# CAN_IFC.net
KiCad netlist of a schematic drawn in Altium Designer
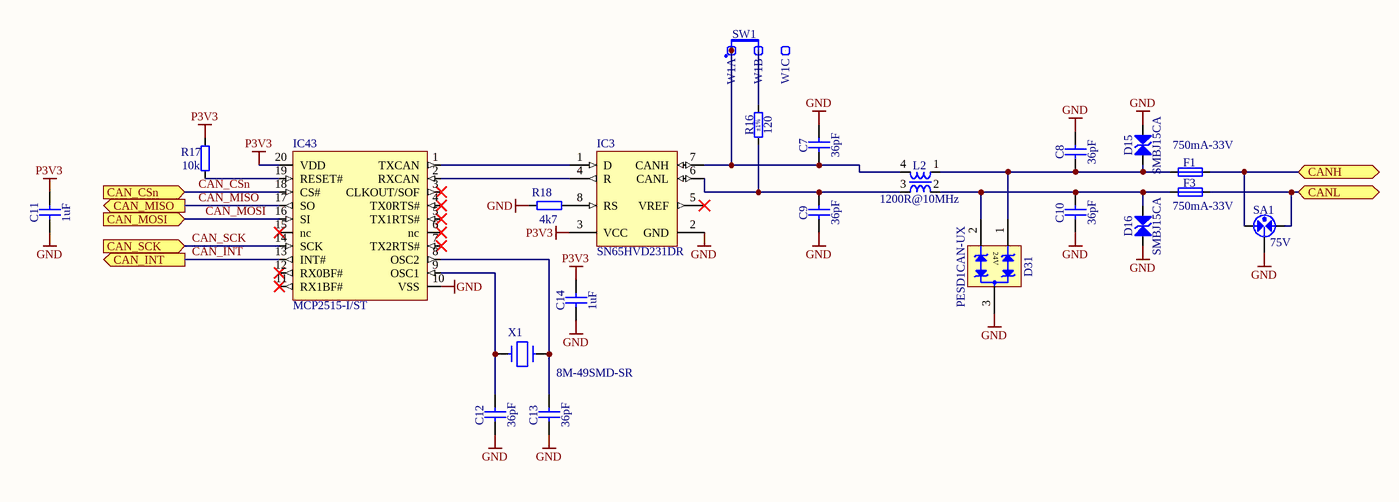
[diagram p0: CAN_IFC.SchDoc]

(export (version "E")
  (design (tool "Eeschema 10.0.6"))
  (components
    (comp (ref "C7")
      (value "36pF")
      (footprint "CAPC1608X87N")
      (description "Non-polarised capacitor")
      (fields
        (field (name "PART NUMBER") "CC0603_36PF_50V_5%_C0G")
        (field (name "VOLTAGE") "50V")
        (field (name "AUTHOR") "CERN DEM HF")
      )
      (libsource (lib "Capacitors") (part "Capacitor - non polarized"))
    )
    (comp (ref "C8")
      (value "36pF")
      (footprint "CAPC1608X87N")
      (description "Non-polarised capacitor")
      (fields
        (field (name "PART NUMBER") "CC0603_36PF_50V_5%_C0G")
        (field (name "VOLTAGE") "50V")
        (field (name "AUTHOR") "CERN DEM HF")
      )
      (libsource (lib "Capacitors") (part "Capacitor - non polarized"))
    )
    (comp (ref "C9")
      (value "36pF")
      (footprint "CAPC1608X87N")
      (description "Non-polarised capacitor")
      (fields
        (field (name "PART NUMBER") "CC0603_36PF_50V_5%_C0G")
        (field (name "VOLTAGE") "50V")
        (field (name "AUTHOR") "CERN DEM HF")
      )
      (libsource (lib "Capacitors") (part "Capacitor - non polarized"))
    )
    (comp (ref "C10")
      (value "36pF")
      (footprint "CAPC1608X87N")
      (description "Non-polarised capacitor")
      (fields
        (field (name "PART NUMBER") "CC0603_36PF_50V_5%_C0G")
        (field (name "VOLTAGE") "50V")
        (field (name "AUTHOR") "CERN DEM HF")
      )
      (libsource (lib "Capacitors") (part "Capacitor - non polarized"))
    )
    (comp (ref "C11")
      (value "1uF")
      (footprint "CAPC1608X87N")
      (description "Non-polarised capacitor")
      (fields
        (field (name "PART NUMBER") "CC0603_1UF_25V_10%_X7R")
        (field (name "VOLTAGE") "25V")
        (field (name "AUTHOR") "CERN DEM JLC")
      )
      (libsource (lib "Capacitors") (part "Capacitor - non polarized"))
    )
    (comp (ref "C12")
      (value "36pF")
      (footprint "CAPC1608X87N")
      (description "Non-polarised capacitor")
      (fields
        (field (name "PART NUMBER") "CC0603_36PF_50V_5%_C0G")
        (field (name "VOLTAGE") "50V")
        (field (name "AUTHOR") "CERN DEM HF")
      )
      (libsource (lib "Capacitors") (part "Capacitor - non polarized"))
    )
    (comp (ref "C13")
      (value "36pF")
      (footprint "CAPC1608X87N")
      (description "Non-polarised capacitor")
      (fields
        (field (name "PART NUMBER") "CC0603_36PF_50V_5%_C0G")
        (field (name "VOLTAGE") "50V")
        (field (name "AUTHOR") "CERN DEM HF")
      )
      (libsource (lib "Capacitors") (part "Capacitor - non polarized"))
    )
    (comp (ref "C14")
      (value "1uF")
      (footprint "CAPC1608X87N")
      (description "Non-polarised capacitor")
      (fields
        (field (name "PART NUMBER") "CC0603_1UF_25V_10%_X7R")
        (field (name "VOLTAGE") "25V")
        (field (name "AUTHOR") "CERN DEM JLC")
      )
      (libsource (lib "Capacitors") (part "Capacitor - non polarized"))
    )
    (comp (ref "D15")
      (value "SMBJ15CA")
      (footprint "DIOM5336X265N")
      (description "Transient Voltage Suppressor Diode (Bi-Directional)")
      (fields
        (field (name "VOLTAGE") "15V")
        (field (name "POWER") "600W")
        (field (name "AUTHOR") "CERN DEM JLC")
      )
      (libsource (lib "ICs And Semiconductors") (part "Diode TVS Bi-Directional"))
    )
    (comp (ref "D16")
      (value "SMBJ15CA")
      (footprint "DIOM5336X265N")
      (description "Transient Voltage Suppressor Diode (Bi-Directional)")
      (fields
        (field (name "VOLTAGE") "15V")
        (field (name "POWER") "600W")
        (field (name "AUTHOR") "CERN DEM JLC")
      )
      (libsource (lib "ICs And Semiconductors") (part "Diode TVS Bi-Directional"))
    )
    (comp (ref "D31")
      (value "PESD1CAN-UX")
      (footprint "SOT95P237X112-3N")
      (description "TVS Diode for CAN")
      (fields
        (field (name "VOLTAGE") "24V")
        (field (name "POWER") "400W")
        (field (name "AUTHOR") "CERN DEM JLC")
      )
      (libsource (lib "LIBRARY_SCH") (part "D_TVS_PESD1CAN"))
    )
    (comp (ref "F1")
      (value "750mA-33V")
      (footprint "FUSRC4632X150N")
      (description "Fuse")
      (fields
        (field (name "PART NUMBER") "FUSR1812_LITTELFUSE_miniSMDC075F/33")
        (field (name "MANUFACTURER") "LITTELFUSE")
        (field (name "AUTHOR") "CERN DEM HF")
      )
      (libsource (lib "Eletro-mechanical") (part "Fuse"))
    )
    (comp (ref "F3")
      (value "750mA-33V")
      (footprint "FUSRC4632X150N")
      (description "Fuse")
      (fields
        (field (name "PART NUMBER") "FUSR1812_LITTELFUSE_miniSMDC075F/33")
        (field (name "MANUFACTURER") "LITTELFUSE")
        (field (name "AUTHOR") "CERN DEM HF")
      )
      (libsource (lib "Eletro-mechanical") (part "Fuse"))
    )
    (comp (ref "IC3")
      (value "SN65HVD231DR")
      (footprint "D0008A_L")
      (fields (field (name "MANUFACTURER") "Texas Instruments"))
      (libsource (lib "Altium Content Vault") (part "TI-SN65HVD231-SOIC_D-8"))
    )
    (comp (ref "IC43")
      (value "MCP2515-I/ST")
      (footprint "SOP65P640X110-20N")
      (description "CAN Controller With SPI nterface")
      (fields
        (field (name "MANUFACTURER") "Microchip")
        (field (name "MANUFACTURER PART NUMBER") "MCP2515T-I/ST")
      )
      (libsource (lib "LIBRARY_SCH") (part "IFC_MCP2515_TSSOP"))
    )
    (comp (ref "L2")
      (value "1200R@10MHz")
      (footprint "IND_TDK_ACT45B")
      (description "Inductor Common Mode")
      (fields
        (field (name "PART NUMBER") "IND_TDK_ACT45B-220-2P")
        (field (name "POWER") "200mA")
        (field (name "AUTHOR") "CERN DEM BC")
      )
      (libsource (lib "Inductors & Transformers") (part "Inductor Common Mode 1-4 2-3"))
    )
    (comp (ref "R16")
      (value "120")
      (footprint "RESC3216X65N")
      (description "Resistor - 1%")
      (fields
        (field (name "TOLERANCE") "±1%")
        (field (name "PART NUMBER") "R1206_120R_1%_0.25W_100PPM")
        (field (name "POWER") "0.25W")
        (field (name "AUTHOR") "CERN DEM JLC")
      )
      (libsource (lib "Resistors") (part "Resistor - 1%"))
    )
    (comp (ref "R17")
      (value "10k")
      (footprint "RESC1608X55N")
      (description "Resistor - 1%")
      (fields
        (field (name "PART NUMBER") "R0603_10K_1%_0.1W_100PPM")
        (field (name "POWER") "0.1W")
        (field (name "AUTHOR") "CERN DEM JLC")
      )
      (libsource (lib "Resistors") (part "Resistor - 1%"))
    )
    (comp (ref "R18")
      (value "4k7")
      (footprint "RESC1608X55N")
      (description "Resistor - 1%")
      (fields
        (field (name "PART NUMBER") "R0603_4K7_1%_0.1W_100PPM")
        (field (name "POWER") "0.1W")
        (field (name "AUTHOR") "CERN DEM JLC")
      )
      (libsource (lib "Resistors") (part "Resistor - 1%"))
    )
    (comp (ref "SA1")
      (value "75V")
      (footprint "SAR_BOURNS_2036-xx-SM")
      (description "Surge Arrester")
      (fields
        (field (name "PART NUMBER") "SAR_BOURNS_2036-07-SMLF")
        (field (name "MANUFACTURER") "BOURNS")
        (field (name "AUTHOR") "CERN DEM JLC")
      )
      (libsource (lib "Eletro-mechanical") (part "Surge Arrester Type2"))
    )
    (comp (ref "SW1")
      (value "Jumper Type1")
      (footprint "JUMPER_BLACK_INSULATED_2.54MM")
      (description "Jumper 1 Pin")
      (fields
        (field (name "PART NUMBER") "COMATEL_313.1730.0.00.40.0")
        (field (name "MANUFACTURER") "KONTEK COMATEL")
        (field (name "AUTHOR") "CERN DEM JLC")
      )
      (libsource (lib "Connectors") (part "Jumper Type1"))
    )
    (comp (ref "W1")
      (value "Test Point")
      (footprint "COMATEL_385.0358.1.03.400")
      (description "3 Mini Wire-Wrap Contact Strip Header")
      (fields
        (field (name "PART NUMBER") "COMATEL_385.0358.1.03.400")
        (field (name "MANUFACTURER") "KONTEK COMATEL")
        (field (name "AUTHOR") "CERN DEM JLC")
      )
      (libsource (lib "Connectors") (part "Wire-Wrap Contact x3"))
    )
    (comp (ref "X1")
      (value "8M-49SMD-SR")
      (footprint "HC-49SM")
      (description "8MHz; ±30ppm; 20pF; SMD; HC49SMD")
      (libsource (lib "Crystals_Oscillators") (part "X_CRYSTAL_HC49_SMT"))
    )
  )
  (nets
    (net (code "1") (name "/CANH") (class "Default")
      (node (ref "F1") (pin "2") (pinfunction "2_2") (pintype "passive"))
      (node (ref "SA1") (pin "1") (pinfunction "1_1") (pintype "passive"))
    )
    (net (code "2") (name "/CANL") (class "Default")
      (node (ref "F3") (pin "2") (pinfunction "2_2") (pintype "passive"))
      (node (ref "SA1") (pin "2") (pinfunction "2_2") (pintype "passive"))
    )
    (net (code "3") (name "/CAN_CSn") (class "Default")
      (node (ref "IC43") (pin "18") (pinfunction "CS#_18") (pintype "input"))
    )
    (net (code "4") (name "/CAN_INT") (class "Default")
      (node (ref "IC43") (pin "13") (pinfunction "INT#_13") (pintype "output"))
    )
    (net (code "5") (name "/CAN_MISO") (class "Default")
      (node (ref "IC43") (pin "17") (pinfunction "SO_17") (pintype "output"))
    )
    (net (code "6") (name "/CAN_MOSI") (class "Default")
      (node (ref "IC43") (pin "16") (pinfunction "SI_16") (pintype "input"))
    )
    (net (code "7") (name "/CAN_SCK") (class "Default")
      (node (ref "IC43") (pin "14") (pinfunction "SCK_14") (pintype "input"))
    )
    (net (code "8") (name "GND") (class "Default")
      (node (ref "C10") (pin "1") (pinfunction "1_1") (pintype "passive"))
      (node (ref "C11") (pin "1") (pinfunction "1_1") (pintype "passive"))
      (node (ref "C12") (pin "1") (pinfunction "1_1") (pintype "passive"))
      (node (ref "C13") (pin "1") (pinfunction "1_1") (pintype "passive"))
      (node (ref "C14") (pin "1") (pinfunction "1_1") (pintype "passive"))
      (node (ref "C7") (pin "2") (pinfunction "2_2") (pintype "passive"))
      (node (ref "C8") (pin "2") (pinfunction "2_2") (pintype "passive"))
      (node (ref "C9") (pin "1") (pinfunction "1_1") (pintype "passive"))
      (node (ref "D15") (pin "2") (pinfunction "2_2") (pintype "passive"))
      (node (ref "D16") (pin "1") (pinfunction "1_1") (pintype "passive"))
      (node (ref "D31") (pin "3") (pinfunction "GND_3") (pintype "passive"))
      (node (ref "IC3") (pin "2") (pinfunction "GND_2") (pintype "power_in"))
      (node (ref "IC43") (pin "10") (pinfunction "VSS_10") (pintype "power_in"))
      (node (ref "R18") (pin "2") (pinfunction "2_2") (pintype "passive"))
      (node (ref "SA1") (pin "3") (pinfunction "3_3") (pintype "passive"))
    )
    (net (code "9") (name "Net-(D31-I{slash}O1)") (class "Default")
      (node (ref "C8") (pin "1") (pinfunction "1_1") (pintype "passive"))
      (node (ref "D15") (pin "1") (pinfunction "1_1") (pintype "passive"))
      (node (ref "D31") (pin "1") (pinfunction "I/O1_1") (pintype "passive"))
      (node (ref "F1") (pin "1") (pinfunction "1_1") (pintype "passive"))
      (node (ref "L2") (pin "1") (pinfunction "1_1") (pintype "passive"))
    )
    (net (code "10") (name "Net-(D31-I{slash}O2)") (class "Default")
      (node (ref "C10") (pin "2") (pinfunction "2_2") (pintype "passive"))
      (node (ref "D16") (pin "2") (pinfunction "2_2") (pintype "passive"))
      (node (ref "D31") (pin "2") (pinfunction "I/O2_2") (pintype "passive"))
      (node (ref "F3") (pin "1") (pinfunction "1_1") (pintype "passive"))
      (node (ref "L2") (pin "2") (pinfunction "2_2") (pintype "passive"))
    )
    (net (code "11") (name "Net-(IC3-CANH)") (class "Default")
      (node (ref "C7") (pin "1") (pinfunction "1_1") (pintype "passive"))
      (node (ref "IC3") (pin "7") (pinfunction "CANH_7") (pintype "bidirectional"))
      (node (ref "L2") (pin "4") (pinfunction "4_4") (pintype "passive"))
      (node (ref "SW1") (pin "1") (pinfunction "1_1") (pintype "bidirectional"))
      (node (ref "W1") (pin "1") (pinfunction "1_1") (pintype "bidirectional"))
    )
    (net (code "12") (name "Net-(IC3-CANL)") (class "Default")
      (node (ref "C9") (pin "2") (pinfunction "2_2") (pintype "passive"))
      (node (ref "IC3") (pin "6") (pinfunction "CANL_6") (pintype "bidirectional"))
      (node (ref "L2") (pin "3") (pinfunction "3_3") (pintype "passive"))
      (node (ref "R16") (pin "1") (pinfunction "1_1") (pintype "passive"))
    )
    (net (code "13") (name "Net-(IC3-D)") (class "Default")
      (node (ref "IC3") (pin "1") (pinfunction "D_1") (pintype "input"))
      (node (ref "IC43") (pin "1") (pinfunction "TXCAN_1") (pintype "output"))
    )
    (net (code "14") (name "Net-(IC3-R)") (class "Default")
      (node (ref "IC3") (pin "4") (pinfunction "R_4") (pintype "output"))
      (node (ref "IC43") (pin "2") (pinfunction "RXCAN_2") (pintype "input"))
    )
    (net (code "15") (name "Net-(IC3-RS)") (class "Default")
      (node (ref "IC3") (pin "8") (pinfunction "RS_8") (pintype "input"))
      (node (ref "R18") (pin "1") (pinfunction "1_1") (pintype "passive"))
    )
    (net (code "16") (name "Net-(IC43-OSC1)") (class "Default")
      (node (ref "C12") (pin "2") (pinfunction "2_2") (pintype "passive"))
      (node (ref "IC43") (pin "9") (pinfunction "OSC1_9") (pintype "input"))
      (node (ref "X1") (pin "1") (pinfunction "1_1") (pintype "passive"))
    )
    (net (code "17") (name "Net-(IC43-OSC2)") (class "Default")
      (node (ref "C13") (pin "2") (pinfunction "2_2") (pintype "passive"))
      (node (ref "IC43") (pin "8") (pinfunction "OSC2_8") (pintype "output"))
      (node (ref "X1") (pin "2") (pinfunction "2_2") (pintype "passive"))
    )
    (net (code "18") (name "Net-(IC43-RESET#)") (class "Default")
      (node (ref "IC43") (pin "19") (pinfunction "RESET#_19") (pintype "input"))
      (node (ref "R17") (pin "1") (pinfunction "1_1") (pintype "passive"))
    )
    (net (code "19") (name "Net-(R16-Pad2)") (class "Default")
      (node (ref "R16") (pin "2") (pinfunction "2_2") (pintype "passive"))
      (node (ref "W1") (pin "2") (pinfunction "2_2") (pintype "bidirectional"))
    )
    (net (code "20") (name "P3V3") (class "Default")
      (node (ref "C11") (pin "2") (pinfunction "2_2") (pintype "passive"))
      (node (ref "C14") (pin "2") (pinfunction "2_2") (pintype "passive"))
      (node (ref "IC3") (pin "3") (pinfunction "VCC_3") (pintype "power_in"))
      (node (ref "IC43") (pin "20") (pinfunction "VDD_20") (pintype "power_in"))
      (node (ref "R17") (pin "2") (pinfunction "2_2") (pintype "passive"))
    )
    (net (code "21") (name "unconnected-(IC3-VREF-Pad5)") (class "Default")
      (node (ref "IC3") (pin "5") (pinfunction "VREF_5") (pintype "output+no_connect"))
    )
    (net (code "22") (name "unconnected-(IC43-CLKOUT{slash}SOF-Pad3)") (class "Default")
      (node (ref "IC43") (pin "3") (pinfunction "CLKOUT/SOF_3") (pintype "output+no_connect"))
    )
    (net (code "23") (name "unconnected-(IC43-RX0BF#-Pad12)") (class "Default")
      (node (ref "IC43") (pin "12") (pinfunction "RX0BF#_12") (pintype "output+no_connect"))
    )
    (net (code "24") (name "unconnected-(IC43-RX1BF#-Pad11)") (class "Default")
      (node (ref "IC43") (pin "11") (pinfunction "RX1BF#_11") (pintype "output+no_connect"))
    )
    (net (code "25") (name "unconnected-(IC43-TX0RTS#-Pad4)") (class "Default")
      (node (ref "IC43") (pin "4") (pinfunction "TX0RTS#_4") (pintype "input+no_connect"))
    )
    (net (code "26") (name "unconnected-(IC43-TX1RTS#-Pad5)") (class "Default")
      (node (ref "IC43") (pin "5") (pinfunction "TX1RTS#_5") (pintype "input+no_connect"))
    )
    (net (code "27") (name "unconnected-(IC43-TX2RTS#-Pad7)") (class "Default")
      (node (ref "IC43") (pin "7") (pinfunction "TX2RTS#_7") (pintype "input+no_connect"))
    )
    (net (code "28") (name "unconnected-(IC43-nc-Pad6)") (class "Default")
      (node (ref "IC43") (pin "6") (pinfunction "nc_6") (pintype "passive+no_connect"))
    )
    (net (code "29") (name "unconnected-(IC43-nc-Pad15)") (class "Default")
      (node (ref "IC43") (pin "15") (pinfunction "nc_15") (pintype "passive+no_connect"))
    )
    (net (code "30") (name "unconnected-(W1-Pad3)") (class "Default")
      (node (ref "W1") (pin "3") (pinfunction "3_3") (pintype "bidirectional"))
    )
  )
)
